# fram.net
KiCad netlist of a schematic drawn in Altium Designer
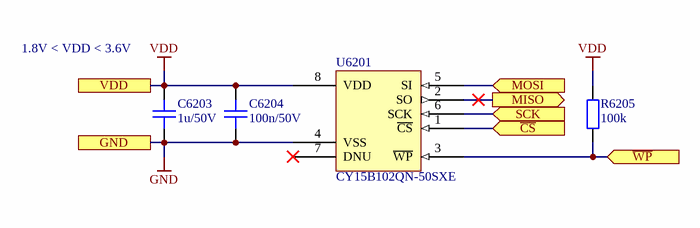
[diagram p0: fram.SchDoc]

(export (version "E")
  (design (tool "Eeschema 10.0.6"))
  (components
    (comp (ref "C6203")
      (value "1u/50V")
      (footprint "CAPC1608X08N")
      (description "MLCC")
      (fields (field (name "PART NUMBER") "gen_C_ceramic_1u_50V_X7R_0603") (field (name "TOLERANCE") "± 10%"))
      (libsource (lib "OE750") (part "C"))
    )
    (comp (ref "C6204")
      (value "100n/50V")
      (footprint "CAPC1005X06N")
      (description "MLCC")
      (fields (field (name "PART NUMBER") "gen_C_ceramic_100n_50V_X7R_0402"))
      (libsource (lib "OE750") (part "C"))
    )
    (comp (ref "R6205")
      (value "100k")
      (footprint "RESC1005X04N")
      (description "SMD Resistor 100k 0402")
      (fields (field (name "PART NUMBER") "gen_R_100k_0402") (field (name "TOLERANCE") "1%"))
      (libsource (lib "OE750") (part "R"))
    )
    (comp (ref "U6201")
      (value "CY15B102QN-50SXE")
      (footprint "CY15B102QN-50SXE")
      (description "Excelon™-Auto 2-Mbit (256K × 8) Automotive-E Serial (SPI) F-RAM")
      (fields (field (name "MANUFACTURER") "Cypress"))
      (libsource (lib "OE750") (part "CY15B102QN-50SXE"))
    )
  )
  (nets
    (net (code "1") (name "/CS") (class "Default")
      (node (ref "U6201") (pin "1") (pinfunction "CS_1") (pintype "input"))
    )
    (net (code "2") (name "/MISO") (class "Default")
      (node (ref "U6201") (pin "2") (pinfunction "SO_2") (pintype "output"))
    )
    (net (code "3") (name "/MOSI") (class "Default")
      (node (ref "U6201") (pin "5") (pinfunction "SI_5") (pintype "input"))
    )
    (net (code "4") (name "/SCK") (class "Default")
      (node (ref "U6201") (pin "6") (pinfunction "SCK_6") (pintype "input"))
    )
    (net (code "5") (name "/WP") (class "Default")
      (node (ref "R6205") (pin "1") (pinfunction "1_1") (pintype "passive"))
      (node (ref "U6201") (pin "3") (pinfunction "WP_3") (pintype "input"))
    )
    (net (code "6") (name "GND") (class "Default")
      (node (ref "C6203") (pin "1") (pinfunction "1_1") (pintype "passive"))
      (node (ref "C6204") (pin "1") (pinfunction "1_1") (pintype "passive"))
      (node (ref "U6201") (pin "4") (pinfunction "VSS_4") (pintype "power_in"))
    )
    (net (code "7") (name "VDD") (class "Default")
      (node (ref "C6203") (pin "2") (pinfunction "2_2") (pintype "passive"))
      (node (ref "C6204") (pin "2") (pinfunction "2_2") (pintype "passive"))
      (node (ref "R6205") (pin "2") (pinfunction "2_2") (pintype "passive"))
      (node (ref "U6201") (pin "8") (pinfunction "VDD_8") (pintype "power_in"))
    )
    (net (code "8") (name "unconnected-(U6201-DNU-Pad7)") (class "Default")
      (node (ref "U6201") (pin "7") (pinfunction "DNU_7") (pintype "passive+no_connect"))
    )
  )
)
